# lora1262f30m.net
KiCad netlist of a schematic drawn in Altium Designer
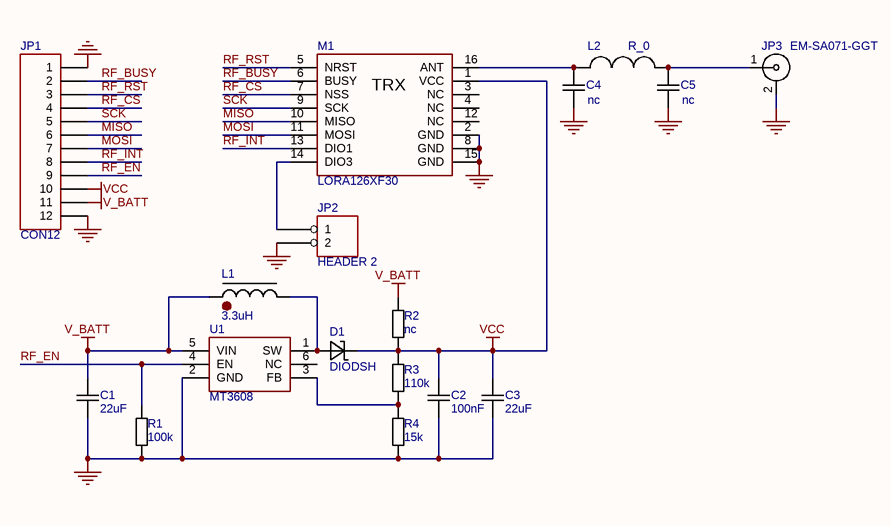
[diagram p0: lora1262f30m.SchDoc]

(export (version "E")
  (design (tool "Eeschema 10.0.6"))
  (components
    (comp (ref "C1")
      (value "22uF")
      (footprint "C-0805")
      (fields (field (name "VOLTAGE") "50V"))
      (libsource (lib "Passive") (part "CAPN"))
    )
    (comp (ref "C2")
      (value "100nF")
      (footprint "C-0603")
      (fields (field (name "VOLTAGE") "50V"))
      (libsource (lib "Passive") (part "CAPN"))
    )
    (comp (ref "C3")
      (value "22uF")
      (footprint "C-0805")
      (fields (field (name "VOLTAGE") "50V"))
      (libsource (lib "Passive") (part "CAPN"))
    )
    (comp (ref "C4")
      (value "nc")
      (footprint "C-0603")
      (fields (field (name "VOLTAGE") "50V"))
      (libsource (lib "Passive") (part "CAPN"))
    )
    (comp (ref "C5")
      (value "nc")
      (footprint "C-0603")
      (fields (field (name "VOLTAGE") "50V"))
      (libsource (lib "Passive") (part "CAPN"))
    )
    (comp (ref "D1") (value "DIODSH") (footprint "D_SMA_NUM") (libsource (lib "Diodes") (part "DIODSH")))
    (comp (ref "JP1")
      (value "CON12")
      (footprint "PBS1-12R")
      (description "Connector")
      (libsource (lib "Connectors") (part "CON12"))
    )
    (comp (ref "JP2")
      (value "HEADER 2")
      (footprint "PLS1-2")
      (libsource (lib "Connectors") (part "HEADER 2"))
    )
    (comp (ref "JP3")
      (value "EM-SA071-GGT")
      (footprint "SMA_F_EDGE")
      (description "SMA Female R/A PCB Mount")
      (libsource (lib "Connectors") (part "SMA"))
    )
    (comp (ref "L1") (value "3.3uH") (footprint "CDRH6D38") (libsource (lib "Passive") (part "L*")))
    (comp (ref "L2") (value "R_0") (footprint "L-0603") (libsource (lib "Passive") (part "L")))
    (comp (ref "M1")
      (value "LORA126XF30")
      (footprint "LGA16_LORA126XF30")
      (libsource (lib "RFmodules") (part "LORA126XF30"))
    )
    (comp (ref "R1") (value "100k") (footprint "R-0603") (libsource (lib "Passive") (part "RES")))
    (comp (ref "R2") (value "nc") (footprint "R-1206") (libsource (lib "Passive") (part "RES")))
    (comp (ref "R3") (value "110k") (footprint "R-0603") (libsource (lib "Passive") (part "RES")))
    (comp (ref "R4") (value "15k") (footprint "R-0603") (libsource (lib "Passive") (part "RES")))
    (comp (ref "U1") (value "MT3608") (footprint "SOT-23-6") (libsource (lib "Power") (part "MT3608")))
  )
  (nets
    (net (code "1") (name "/MISO") (class "Default")
      (node (ref "JP1") (pin "6") (pinfunction "6_6") (pintype "passive"))
      (node (ref "M1") (pin "10") (pinfunction "MISO_10") (pintype "passive"))
    )
    (net (code "2") (name "/MOSI") (class "Default")
      (node (ref "JP1") (pin "7") (pinfunction "7_7") (pintype "passive"))
      (node (ref "M1") (pin "11") (pinfunction "MOSI_11") (pintype "passive"))
    )
    (net (code "3") (name "/RF_BUSY") (class "Default")
      (node (ref "JP1") (pin "2") (pinfunction "2_2") (pintype "passive"))
      (node (ref "M1") (pin "6") (pinfunction "BUSY_6") (pintype "passive"))
    )
    (net (code "4") (name "/RF_CS") (class "Default")
      (node (ref "JP1") (pin "4") (pinfunction "4_4") (pintype "passive"))
      (node (ref "M1") (pin "7") (pinfunction "NSS_7") (pintype "passive"))
    )
    (net (code "5") (name "/RF_EN") (class "Default")
      (node (ref "JP1") (pin "9") (pinfunction "9_9") (pintype "passive"))
      (node (ref "R1") (pin "2") (pinfunction "2_2") (pintype "passive"))
      (node (ref "U1") (pin "4") (pinfunction "EN_4") (pintype "passive"))
    )
    (net (code "6") (name "/RF_INT") (class "Default")
      (node (ref "JP1") (pin "8") (pinfunction "8_8") (pintype "passive"))
      (node (ref "M1") (pin "13") (pinfunction "DIO1_13") (pintype "passive"))
    )
    (net (code "7") (name "/RF_RST") (class "Default")
      (node (ref "JP1") (pin "3") (pinfunction "3_3") (pintype "passive"))
      (node (ref "M1") (pin "5") (pinfunction "NRST_5") (pintype "passive"))
    )
    (net (code "8") (name "/SCK") (class "Default")
      (node (ref "JP1") (pin "5") (pinfunction "5_5") (pintype "passive"))
      (node (ref "M1") (pin "9") (pinfunction "SCK_9") (pintype "passive"))
    )
    (net (code "9") (name "GND") (class "Default")
      (node (ref "C1") (pin "2") (pinfunction "2_2") (pintype "passive"))
      (node (ref "C2") (pin "2") (pinfunction "2_2") (pintype "passive"))
      (node (ref "C3") (pin "2") (pinfunction "2_2") (pintype "passive"))
      (node (ref "C4") (pin "2") (pinfunction "2_2") (pintype "passive"))
      (node (ref "C5") (pin "2") (pinfunction "2_2") (pintype "passive"))
      (node (ref "JP1") (pin "1") (pinfunction "1_1") (pintype "passive"))
      (node (ref "JP1") (pin "12") (pinfunction "12_12") (pintype "passive"))
      (node (ref "JP2") (pin "2") (pinfunction "2_2") (pintype "passive"))
      (node (ref "JP3") (pin "2") (pinfunction "2_2") (pintype "passive"))
      (node (ref "M1") (pin "15") (pinfunction "GND_15") (pintype "passive"))
      (node (ref "M1") (pin "2") (pinfunction "GND_2") (pintype "passive"))
      (node (ref "M1") (pin "8") (pinfunction "GND_8") (pintype "passive"))
      (node (ref "R1") (pin "1") (pinfunction "1_1") (pintype "passive"))
      (node (ref "R4") (pin "1") (pinfunction "1_1") (pintype "passive"))
      (node (ref "U1") (pin "2") (pinfunction "GND_2") (pintype "passive"))
    )
    (net (code "10") (name "Net-(C5-Pad1)") (class "Default")
      (node (ref "C5") (pin "1") (pinfunction "1_1") (pintype "passive"))
      (node (ref "JP3") (pin "1") (pinfunction "1_1") (pintype "passive"))
      (node (ref "L2") (pin "2") (pinfunction "2_2") (pintype "passive"))
    )
    (net (code "11") (name "Net-(M1-ANT)") (class "Default")
      (node (ref "C4") (pin "1") (pinfunction "1_1") (pintype "passive"))
      (node (ref "L2") (pin "1") (pinfunction "1_1") (pintype "passive"))
      (node (ref "M1") (pin "16") (pinfunction "ANT_16") (pintype "passive"))
    )
    (net (code "12") (name "Net-(M1-DIO3)") (class "Default")
      (node (ref "JP2") (pin "1") (pinfunction "1_1") (pintype "passive"))
      (node (ref "M1") (pin "14") (pinfunction "DIO3_14") (pintype "passive"))
    )
    (net (code "13") (name "Net-(U1-FB)") (class "Default")
      (node (ref "R3") (pin "1") (pinfunction "1_1") (pintype "passive"))
      (node (ref "R4") (pin "2") (pinfunction "2_2") (pintype "passive"))
      (node (ref "U1") (pin "3") (pinfunction "FB_3") (pintype "passive"))
    )
    (net (code "14") (name "Net-(U1-SW)") (class "Default")
      (node (ref "D1") (pin "1") (pinfunction "1_1") (pintype "passive"))
      (node (ref "L1") (pin "2") (pinfunction "2_2") (pintype "passive"))
      (node (ref "U1") (pin "1") (pinfunction "SW_1") (pintype "passive"))
    )
    (net (code "15") (name "VCC") (class "Default")
      (node (ref "C2") (pin "1") (pinfunction "1_1") (pintype "passive"))
      (node (ref "C3") (pin "1") (pinfunction "1_1") (pintype "passive"))
      (node (ref "D1") (pin "2") (pinfunction "2_2") (pintype "passive"))
      (node (ref "JP1") (pin "10") (pinfunction "10_10") (pintype "passive"))
      (node (ref "M1") (pin "1") (pinfunction "VCC_1") (pintype "passive"))
      (node (ref "R2") (pin "1") (pinfunction "1_1") (pintype "passive"))
      (node (ref "R3") (pin "2") (pinfunction "2_2") (pintype "passive"))
    )
    (net (code "16") (name "V_BATT") (class "Default")
      (node (ref "C1") (pin "1") (pinfunction "1_1") (pintype "passive"))
      (node (ref "JP1") (pin "11") (pinfunction "11_11") (pintype "passive"))
      (node (ref "L1") (pin "1") (pinfunction "1_1") (pintype "passive"))
      (node (ref "R2") (pin "2") (pinfunction "2_2") (pintype "passive"))
      (node (ref "U1") (pin "5") (pinfunction "VIN_5") (pintype "passive"))
    )
    (net (code "17") (name "unconnected-(M1-NC-Pad3)") (class "Default")
      (node (ref "M1") (pin "3") (pinfunction "NC_3") (pintype "passive"))
    )
    (net (code "18") (name "unconnected-(M1-NC-Pad4)") (class "Default")
      (node (ref "M1") (pin "4") (pinfunction "NC_4") (pintype "passive"))
    )
    (net (code "19") (name "unconnected-(M1-NC-Pad12)") (class "Default")
      (node (ref "M1") (pin "12") (pinfunction "NC_12") (pintype "passive"))
    )
    (net (code "20") (name "unconnected-(U1-NC-Pad6)") (class "Default")
      (node (ref "U1") (pin "6") (pinfunction "NC_6") (pintype "passive"))
    )
  )
)
